# FullyDifferentialOpAmps.net
KiCad netlist of a schematic drawn in Altium Designer
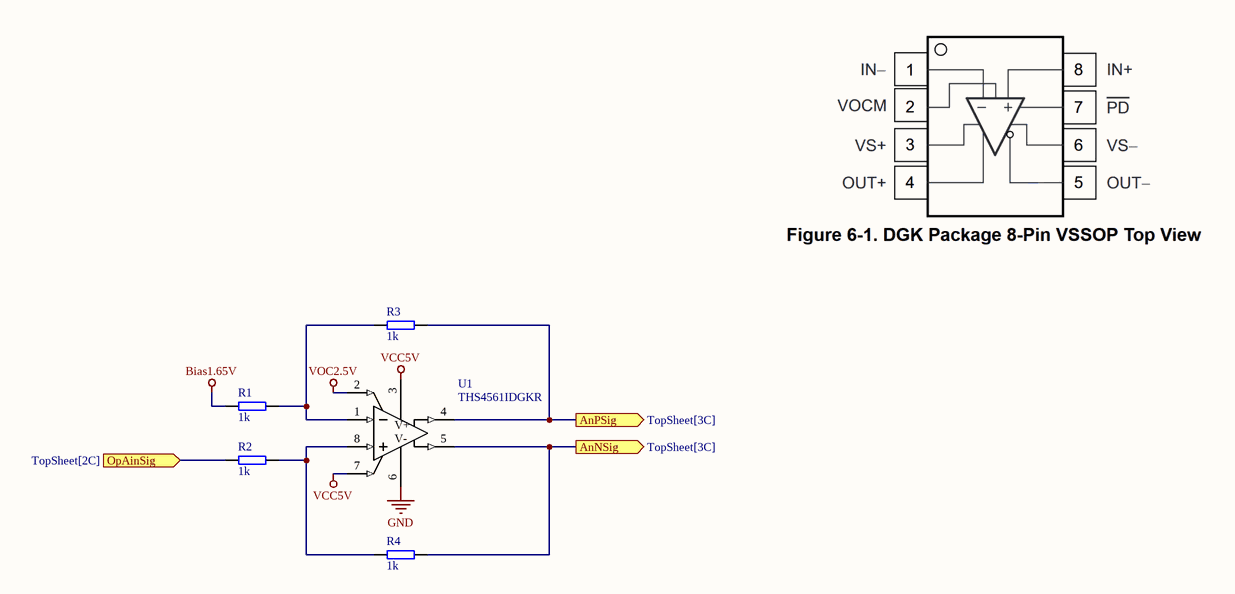
[diagram p0: FullyDifferentialOpAmps.SchDoc]

(export (version "E")
  (design (tool "Eeschema 10.0.6"))
  (components
    (comp (ref "R1")
      (value "1k")
      (footprint "RES 0603_1608")
      (description "SMD resistor E24 series")
      (fields
        (field (name "MANUFACTURER PART NUMBER") "0603WAF1001T5E")
        (field (name "MANUFACTURER") "UNI-ROYAL")
        (field (name "CREATED FROM") "AGeiger")
      )
      (libsource (lib "user") (part "Resistor"))
    )
    (comp (ref "R2")
      (value "1k")
      (footprint "RES 0603_1608")
      (description "SMD resistor E24 series")
      (fields
        (field (name "MANUFACTURER PART NUMBER") "0603WAF1001T5E")
        (field (name "MANUFACTURER") "UNI-ROYAL")
        (field (name "CREATED FROM") "AGeiger")
      )
      (libsource (lib "user") (part "Resistor"))
    )
    (comp (ref "R3")
      (value "1k")
      (footprint "RES 0603_1608")
      (description "SMD resistor E24 series")
      (fields
        (field (name "MANUFACTURER PART NUMBER") "0603WAF1001T5E")
        (field (name "MANUFACTURER") "UNI-ROYAL")
        (field (name "CREATED FROM") "AGeiger")
      )
      (libsource (lib "user") (part "Resistor"))
    )
    (comp (ref "R4")
      (value "1k")
      (footprint "RES 0603_1608")
      (description "SMD resistor E24 series")
      (fields
        (field (name "MANUFACTURER PART NUMBER") "0603WAF1001T5E")
        (field (name "MANUFACTURER") "UNI-ROYAL")
        (field (name "CREATED FROM") "AGeiger")
      )
      (libsource (lib "user") (part "Resistor"))
    )
    (comp (ref "U1")
      (value "THS4561IDGKR")
      (footprint "DGK0008A_N")
      (description "No Description Available")
      (libsource (lib "HLU TUM") (part "THS4561IDGKR"))
    )
  )
  (nets
    (net (code "1") (name "/AnNSig") (class "Default")
      (node (ref "R4") (pin "2") (pinfunction "2_2") (pintype "passive"))
      (node (ref "U1") (pin "5") (pinfunction "VOUT-_5") (pintype "output"))
    )
    (net (code "2") (name "/AnPSig") (class "Default")
      (node (ref "R3") (pin "2") (pinfunction "2_2") (pintype "passive"))
      (node (ref "U1") (pin "4") (pinfunction "VOUT+_4") (pintype "output"))
    )
    (net (code "3") (name "/OpAinSig") (class "Default")
      (node (ref "R2") (pin "1") (pinfunction "1_1") (pintype "passive"))
    )
    (net (code "4") (name "Bias1.65V") (class "Default")
      (node (ref "R1") (pin "1") (pinfunction "1_1") (pintype "passive"))
    )
    (net (code "5") (name "GND") (class "Default")
      (node (ref "U1") (pin "6") (pinfunction "VS-_6") (pintype "power_in"))
    )
    (net (code "6") (name "Net-(U1-VIN+)") (class "Default")
      (node (ref "R2") (pin "2") (pinfunction "2_2") (pintype "passive"))
      (node (ref "R4") (pin "1") (pinfunction "1_1") (pintype "passive"))
      (node (ref "U1") (pin "8") (pinfunction "VIN+_8") (pintype "input"))
    )
    (net (code "7") (name "Net-(U1-VIN-)") (class "Default")
      (node (ref "R1") (pin "2") (pinfunction "2_2") (pintype "passive"))
      (node (ref "R3") (pin "1") (pinfunction "1_1") (pintype "passive"))
      (node (ref "U1") (pin "1") (pinfunction "VIN-_1") (pintype "input"))
    )
    (net (code "8") (name "VCC5V") (class "Default")
      (node (ref "U1") (pin "3") (pinfunction "VS+_3") (pintype "power_in"))
      (node (ref "U1") (pin "7") (pinfunction "PD_N_7") (pintype "input"))
    )
    (net (code "9") (name "VOC2.5V") (class "Default")
      (node (ref "U1") (pin "2") (pinfunction "VOCM_2") (pintype "input"))
    )
  )
)
